# EMC1833T.net
KiCad netlist of a schematic drawn in Altium Designer
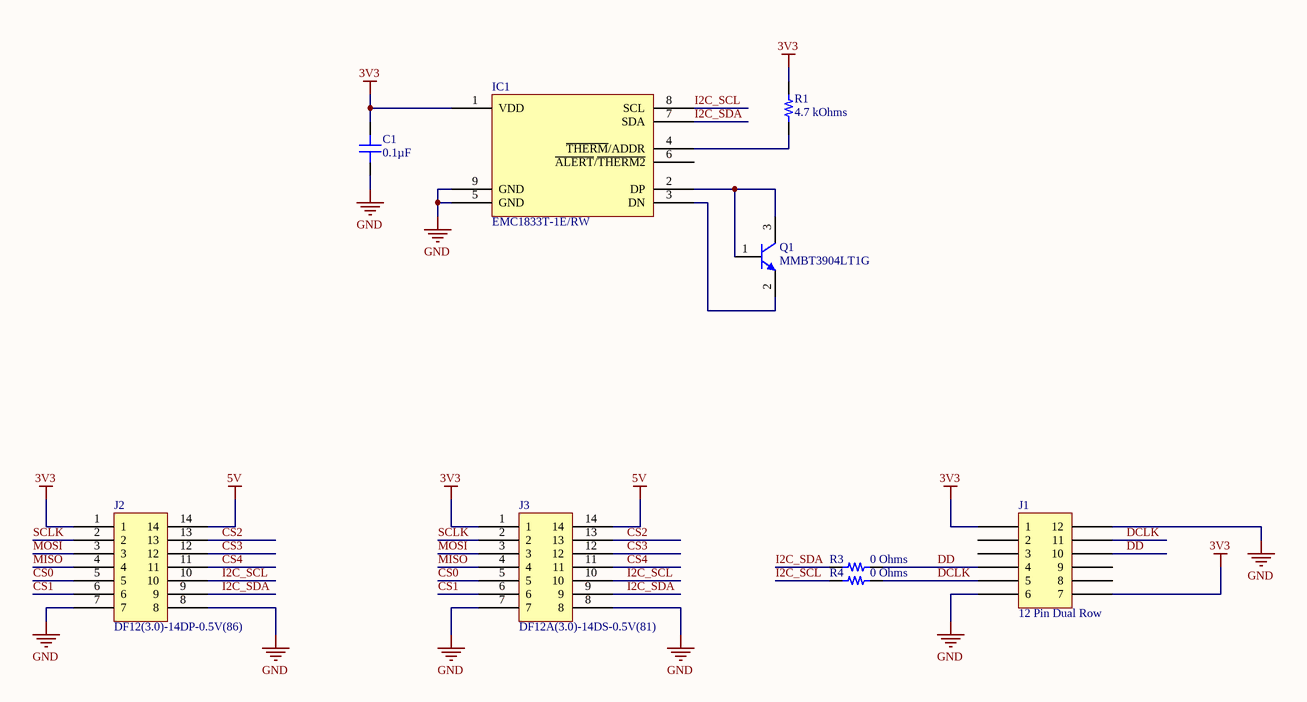
[diagram p0: EMC1833T.SchDoc]

(export (version "E")
  (design (tool "Eeschema 10.0.6"))
  (components
    (comp (ref "C1")
      (value "0.1µF")
      (footprint "CAP 0603_1608")
      (description "CAP CER 0.1UF 16V Y5V 0603")
      (fields (field (name "PART NUMBER") "CC0603ZRY5V7BB104") (field (name "MANUFACTURER") "Yageo"))
      (libsource (lib "altiumlibrary.com") (part "Capacitor"))
    )
    (comp (ref "IC1")
      (value "EMC1833T-1E/RW")
      (footprint "MICROCHIP WDFN-8 2x2MM")
      (description "1.8V 3 CHANNEL TEMP SENSOR I2C 2")
      (fields (field (name "MANUFACTURER") "Microchip Technology"))
      (libsource (lib "altiumlibrary.com") (part "Microchip EMC1833"))
    )
    (comp (ref "J1")
      (value "12 Pin Dual Row")
      (footprint "TE 5650118-3 Card Edge")
      (libsource (lib "CelestialUseful") (part "12 Pin Dual Row"))
    )
    (comp (ref "J2")
      (value "DF12(3.0)-14DP-0.5V(86)")
      (footprint "HIROSE DF12 3.0-14DP-0.5V 86")
      (description "CONN HDR 14POS SMD GOLD")
      (fields (field (name "MANUFACTURER") "Hirose Electric Co Ltd"))
      (libsource (lib "altiumlibrary.com") (part "14 Pin Dual Row"))
    )
    (comp (ref "J3")
      (value "DF12A(3.0)-14DS-0.5V(81)")
      (footprint "HIROSE DF12A 3.0-14DS-0.5V 81")
      (description "CONN RCPT 14POS SMD GOLD")
      (fields (field (name "MANUFACTURER") "Hirose Electric Co Ltd"))
      (libsource (lib "altiumlibrary.com") (part "14 Pin Dual Row"))
    )
    (comp (ref "Q1")
      (value "MMBT3904LT1G")
      (footprint "ON SEMI SOT-23-3")
      (description "TRANS NPN 40V 0.2A SOT23")
      (fields (field (name "MANUFACTURER") "ON Semiconductor"))
      (libsource (lib "altiumlibrary.com") (part "ON SEMI NPN SOT-23-3"))
    )
    (comp (ref "R1")
      (value "4.7 kOhms")
      (footprint "RES 0603_1608")
      (description "RES SMD 4.7K OHM 1% 1/10W 0603")
      (fields
        (field (name "PART NUMBER") "ERJ-3EKF4701V")
        (field (name "MANUFACTURER") "Panasonic Electronic Components")
      )
      (libsource (lib "altiumlibrary.com") (part "Resistor"))
    )
    (comp (ref "R3")
      (value "0 Ohms")
      (footprint "RES 0603_1608")
      (description "RES SMD 0 OHM JUMPER 1/10W 0603")
      (fields
        (field (name "PART NUMBER") "ERJ-3GEY0R00V")
        (field (name "MANUFACTURER") "Panasonic Electronic Components")
      )
      (libsource (lib "altiumlibrary.com") (part "Resistor"))
    )
    (comp (ref "R4")
      (value "0 Ohms")
      (footprint "RES 0603_1608")
      (description "RES SMD 0 OHM JUMPER 1/10W 0603")
      (fields
        (field (name "PART NUMBER") "ERJ-3GEY0R00V")
        (field (name "MANUFACTURER") "Panasonic Electronic Components")
      )
      (libsource (lib "altiumlibrary.com") (part "Resistor"))
    )
  )
  (nets
    (net (code "1") (name "/CS0") (class "Default")
      (node (ref "J2") (pin "5") (pinfunction "5_5") (pintype "passive"))
      (node (ref "J3") (pin "5") (pinfunction "5_5") (pintype "passive"))
    )
    (net (code "2") (name "/CS1") (class "Default")
      (node (ref "J2") (pin "6") (pinfunction "6_6") (pintype "passive"))
      (node (ref "J3") (pin "6") (pinfunction "6_6") (pintype "passive"))
    )
    (net (code "3") (name "/CS2") (class "Default")
      (node (ref "J2") (pin "13") (pinfunction "13_13") (pintype "passive"))
      (node (ref "J3") (pin "13") (pinfunction "13_13") (pintype "passive"))
    )
    (net (code "4") (name "/CS3") (class "Default")
      (node (ref "J2") (pin "12") (pinfunction "12_12") (pintype "passive"))
      (node (ref "J3") (pin "12") (pinfunction "12_12") (pintype "passive"))
    )
    (net (code "5") (name "/CS4") (class "Default")
      (node (ref "J2") (pin "11") (pinfunction "11_11") (pintype "passive"))
      (node (ref "J3") (pin "11") (pinfunction "11_11") (pintype "passive"))
    )
    (net (code "6") (name "/DCLK") (class "Default")
      (node (ref "J1") (pin "11") (pinfunction "11_11") (pintype "passive"))
      (node (ref "J1") (pin "5") (pinfunction "5_5") (pintype "passive"))
      (node (ref "R4") (pin "2") (pinfunction "2_2") (pintype "passive"))
    )
    (net (code "7") (name "/DD") (class "Default")
      (node (ref "J1") (pin "10") (pinfunction "10_10") (pintype "passive"))
      (node (ref "J1") (pin "4") (pinfunction "4_4") (pintype "passive"))
      (node (ref "R3") (pin "2") (pinfunction "2_2") (pintype "passive"))
    )
    (net (code "8") (name "/I2C_SCL") (class "Default")
      (node (ref "IC1") (pin "8") (pinfunction "SCL_8") (pintype "passive"))
      (node (ref "J2") (pin "10") (pinfunction "10_10") (pintype "passive"))
      (node (ref "J3") (pin "10") (pinfunction "10_10") (pintype "passive"))
      (node (ref "R4") (pin "1") (pinfunction "1_1") (pintype "passive"))
    )
    (net (code "9") (name "/I2C_SDA") (class "Default")
      (node (ref "IC1") (pin "7") (pinfunction "SDA_7") (pintype "passive"))
      (node (ref "J2") (pin "9") (pinfunction "9_9") (pintype "passive"))
      (node (ref "J3") (pin "9") (pinfunction "9_9") (pintype "passive"))
      (node (ref "R3") (pin "1") (pinfunction "1_1") (pintype "passive"))
    )
    (net (code "10") (name "/MISO") (class "Default")
      (node (ref "J2") (pin "4") (pinfunction "4_4") (pintype "passive"))
      (node (ref "J3") (pin "4") (pinfunction "4_4") (pintype "passive"))
    )
    (net (code "11") (name "/MOSI") (class "Default")
      (node (ref "J2") (pin "3") (pinfunction "3_3") (pintype "passive"))
      (node (ref "J3") (pin "3") (pinfunction "3_3") (pintype "passive"))
    )
    (net (code "12") (name "/SCLK") (class "Default")
      (node (ref "J2") (pin "2") (pinfunction "2_2") (pintype "passive"))
      (node (ref "J3") (pin "2") (pinfunction "2_2") (pintype "passive"))
    )
    (net (code "13") (name "3V3") (class "Default")
      (node (ref "C1") (pin "1") (pinfunction "1_1") (pintype "passive"))
      (node (ref "IC1") (pin "1") (pinfunction "VDD_1") (pintype "passive"))
      (node (ref "J1") (pin "1") (pinfunction "1_1") (pintype "passive"))
      (node (ref "J1") (pin "7") (pinfunction "7_7") (pintype "passive"))
      (node (ref "J2") (pin "1") (pinfunction "1_1") (pintype "passive"))
      (node (ref "J3") (pin "1") (pinfunction "1_1") (pintype "passive"))
      (node (ref "R1") (pin "2") (pinfunction "2_2") (pintype "passive"))
    )
    (net (code "14") (name "5V") (class "Default")
      (node (ref "J2") (pin "14") (pinfunction "14_14") (pintype "passive"))
      (node (ref "J3") (pin "14") (pinfunction "14_14") (pintype "passive"))
    )
    (net (code "15") (name "GND") (class "Default")
      (node (ref "C1") (pin "2") (pinfunction "2_2") (pintype "passive"))
      (node (ref "IC1") (pin "5") (pinfunction "GND_5") (pintype "passive"))
      (node (ref "IC1") (pin "9") (pinfunction "GND_9") (pintype "passive"))
      (node (ref "J1") (pin "12") (pinfunction "12_12") (pintype "passive"))
      (node (ref "J1") (pin "6") (pinfunction "6_6") (pintype "passive"))
      (node (ref "J2") (pin "7") (pinfunction "7_7") (pintype "passive"))
      (node (ref "J2") (pin "8") (pinfunction "8_8") (pintype "passive"))
      (node (ref "J3") (pin "7") (pinfunction "7_7") (pintype "passive"))
      (node (ref "J3") (pin "8") (pinfunction "8_8") (pintype "passive"))
    )
    (net (code "16") (name "Net-(IC1-DN)") (class "Default")
      (node (ref "IC1") (pin "3") (pinfunction "DN_3") (pintype "passive"))
      (node (ref "Q1") (pin "2") (pinfunction "E_2") (pintype "passive"))
    )
    (net (code "17") (name "Net-(IC1-DP)") (class "Default")
      (node (ref "IC1") (pin "2") (pinfunction "DP_2") (pintype "passive"))
      (node (ref "Q1") (pin "1") (pinfunction "B_1") (pintype "passive"))
      (node (ref "Q1") (pin "3") (pinfunction "C_3") (pintype "passive"))
    )
    (net (code "18") (name "Net-(IC1-~{THERM}{slash}ADDR)") (class "Default")
      (node (ref "IC1") (pin "4") (pinfunction "~{THERM}/ADDR_4") (pintype "passive"))
      (node (ref "R1") (pin "1") (pinfunction "1_1") (pintype "passive"))
    )
    (net (code "19") (name "unconnected-(IC1-~{ALERT}{slash}~{THERM2}-Pad6)") (class "Default")
      (node (ref "IC1") (pin "6") (pinfunction "~{ALERT}/~{THERM2}_6") (pintype "passive"))
    )
    (net (code "20") (name "unconnected-(J1-Pad2)") (class "Default")
      (node (ref "J1") (pin "2") (pinfunction "2_2") (pintype "passive"))
    )
    (net (code "21") (name "unconnected-(J1-Pad3)") (class "Default")
      (node (ref "J1") (pin "3") (pinfunction "3_3") (pintype "passive"))
    )
    (net (code "22") (name "unconnected-(J1-Pad8)") (class "Default")
      (node (ref "J1") (pin "8") (pinfunction "8_8") (pintype "passive"))
    )
    (net (code "23") (name "unconnected-(J1-Pad9)") (class "Default")
      (node (ref "J1") (pin "9") (pinfunction "9_9") (pintype "passive"))
    )
  )
)
